# IF_TX.net
KiCad netlist of a schematic drawn in Altium Designer
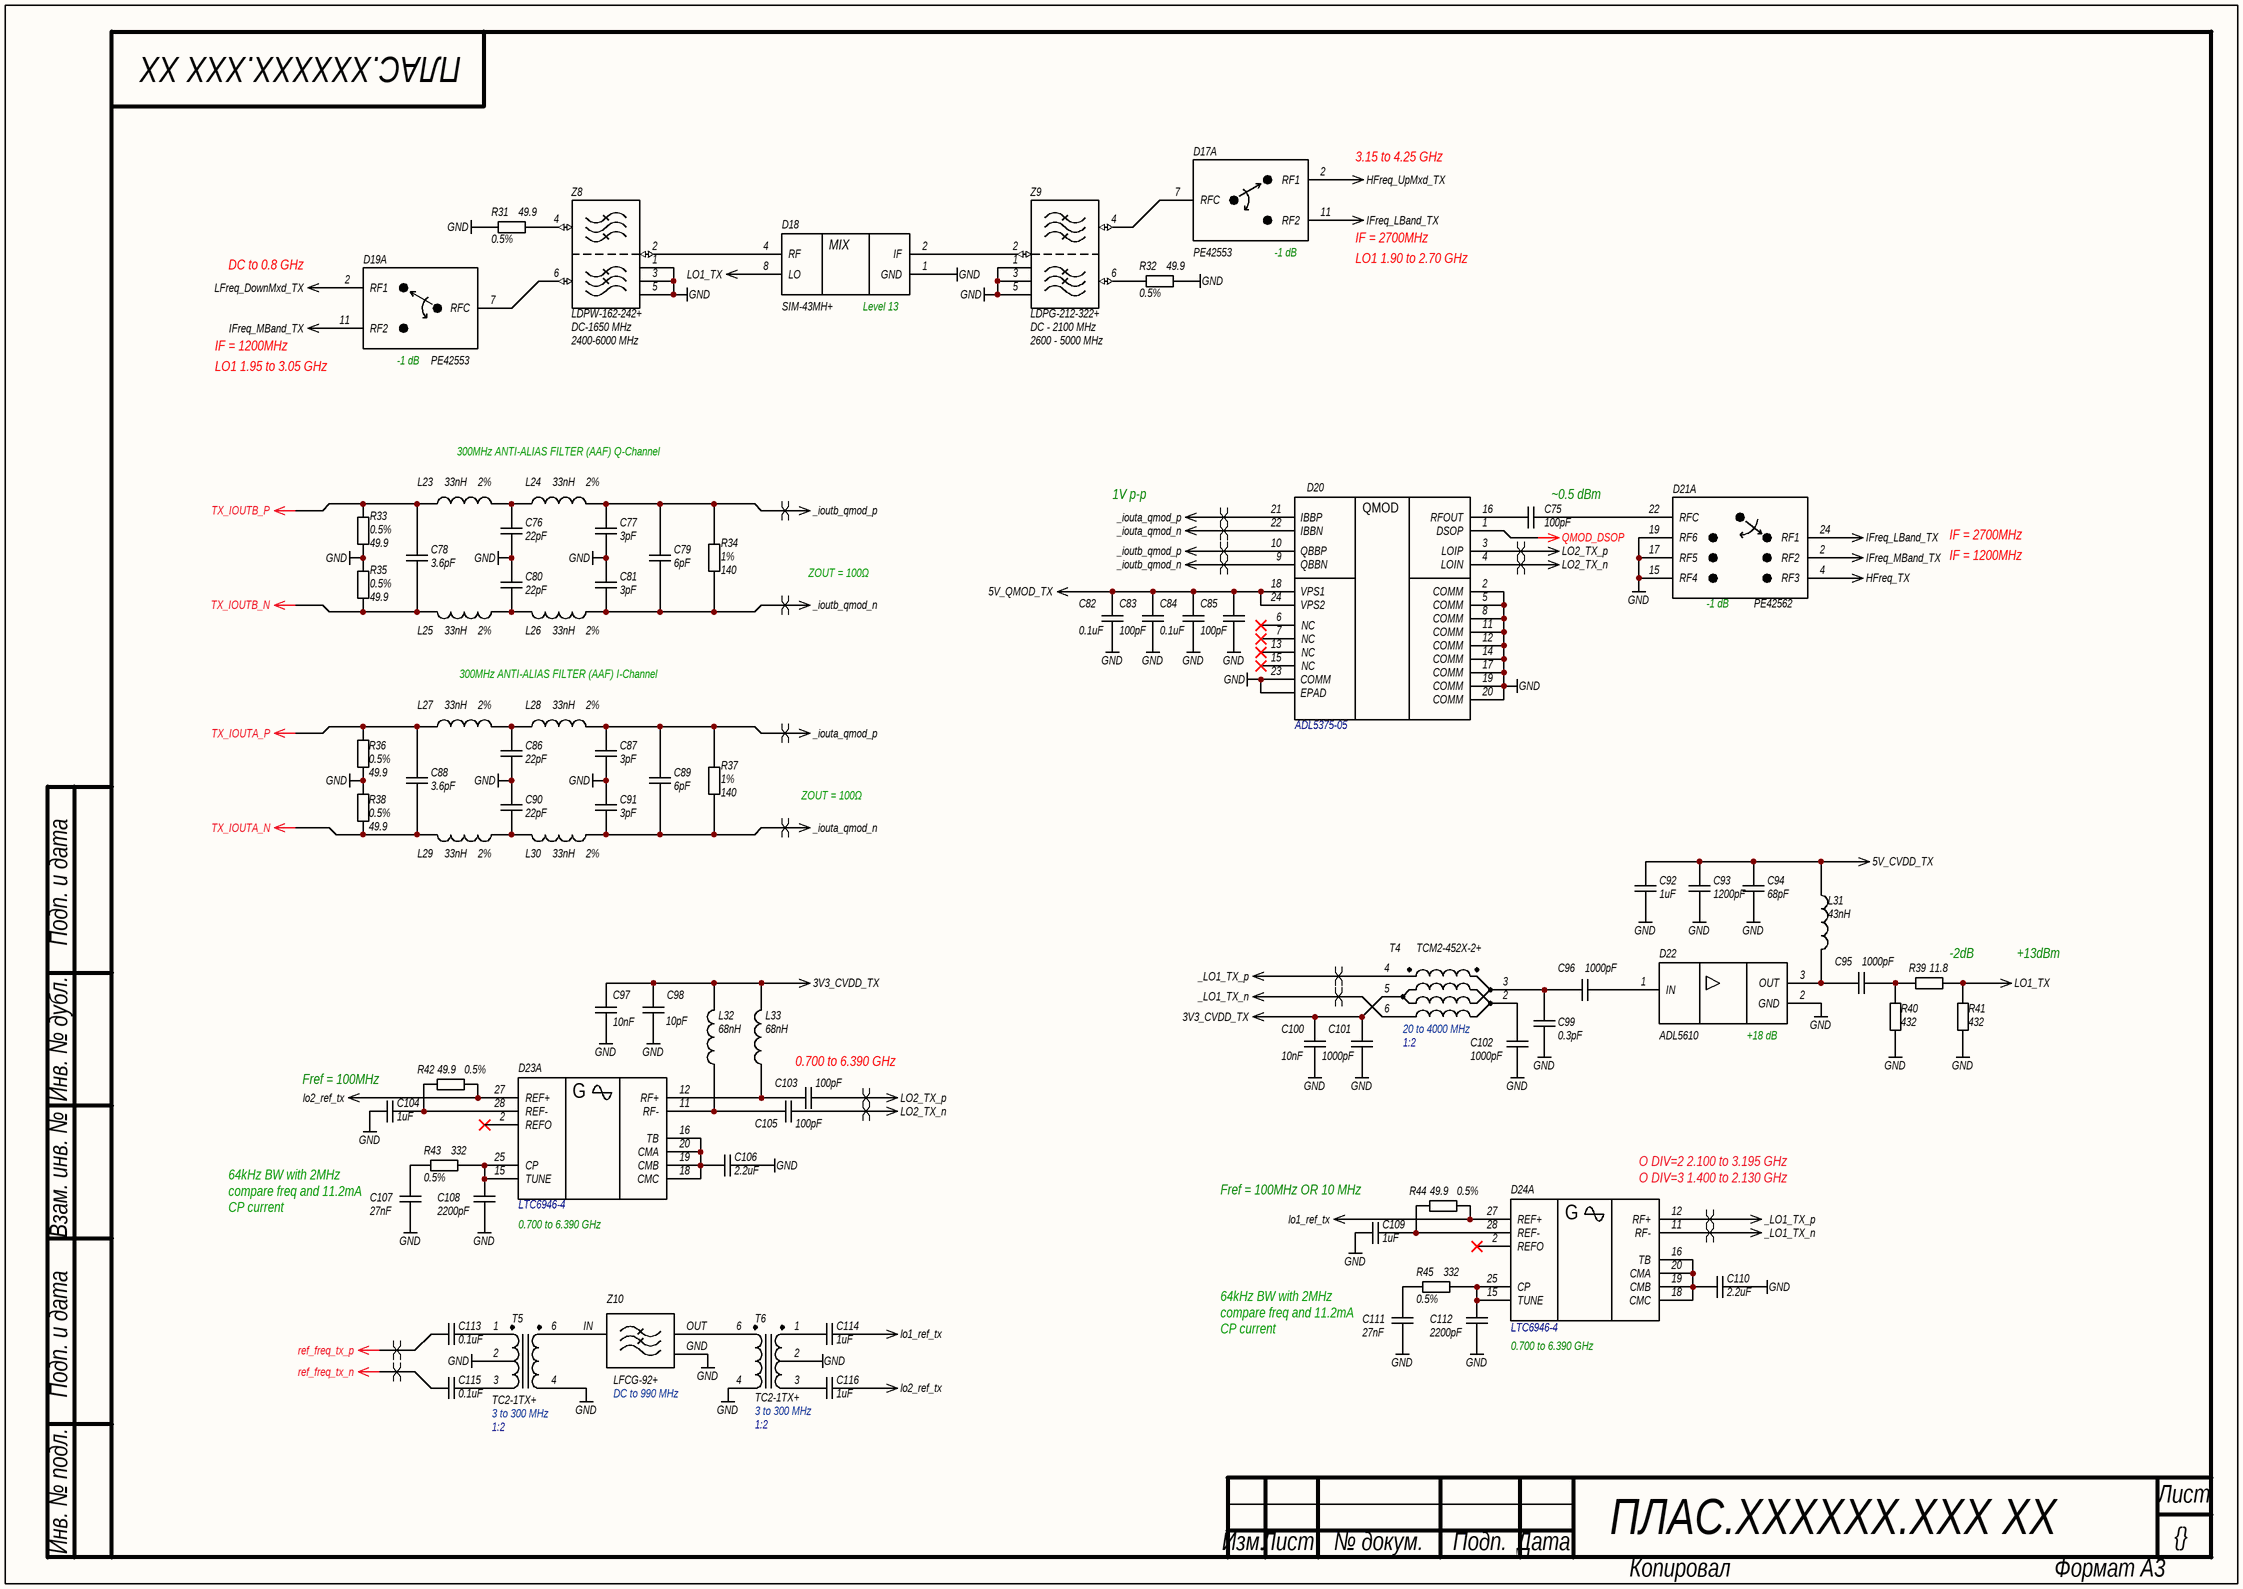
[diagram p0: IF_TX.SchDoc]

(export (version "E")
  (design (tool "Eeschema 10.0.6"))
  (components
    (comp (ref "C75")
      (value "100pF")
      (footprint "C0402")
      (description "SMD Capacitor")
      (fields (field (name "MANUFACTURER") "Murata") (field (name "TOLERANCE") "1%"))
      (libsource (lib "Kintex_SDR") (part "CAP"))
    )
    (comp (ref "C76")
      (value "22pF")
      (footprint "C0402")
      (description "SMD Capacitor")
      (fields (field (name "MANUFACTURER") "Murata") (field (name "TOLERANCE") "1%"))
      (libsource (lib "Kintex_SDR") (part "CAP"))
    )
    (comp (ref "C77")
      (value "3pF")
      (footprint "C0402")
      (description "SMD Capacitor")
      (fields (field (name "MANUFACTURER") "Murata") (field (name "TOLERANCE") "±0.25pF"))
      (libsource (lib "Kintex_SDR") (part "CAP"))
    )
    (comp (ref "C78")
      (value "3.6pF")
      (footprint "C0402")
      (description "SMD Capacitor")
      (fields (field (name "MANUFACTURER") "Murata") (field (name "TOLERANCE") "±0.25pF"))
      (libsource (lib "Kintex_SDR") (part "CAP"))
    )
    (comp (ref "C79")
      (value "6pF")
      (footprint "C0402")
      (description "SMD Capacitor")
      (fields (field (name "MANUFACTURER") "Murata") (field (name "TOLERANCE") "±0.5pF"))
      (libsource (lib "Kintex_SDR") (part "CAP"))
    )
    (comp (ref "C80")
      (value "22pF")
      (footprint "C0402")
      (description "SMD Capacitor")
      (fields (field (name "MANUFACTURER") "Murata") (field (name "TOLERANCE") "1%"))
      (libsource (lib "Kintex_SDR") (part "CAP"))
    )
    (comp (ref "C81")
      (value "3pF")
      (footprint "C0402")
      (description "SMD Capacitor")
      (fields (field (name "MANUFACTURER") "Murata") (field (name "TOLERANCE") "±0.25pF"))
      (libsource (lib "Kintex_SDR") (part "CAP"))
    )
    (comp (ref "C82")
      (value "0.1uF")
      (footprint "C0402")
      (description "SMD Capacitor")
      (fields (field (name "MANUFACTURER") "Murata") (field (name "TOLERANCE") "10%"))
      (libsource (lib "Kintex_SDR") (part "CAP"))
    )
    (comp (ref "C83")
      (value "100pF")
      (footprint "C0402")
      (description "SMD Capacitor")
      (fields (field (name "MANUFACTURER") "Murata") (field (name "TOLERANCE") "1%"))
      (libsource (lib "Kintex_SDR") (part "CAP"))
    )
    (comp (ref "C84")
      (value "0.1uF")
      (footprint "C0402")
      (description "SMD Capacitor")
      (fields (field (name "MANUFACTURER") "Murata") (field (name "TOLERANCE") "10%"))
      (libsource (lib "Kintex_SDR") (part "CAP"))
    )
    (comp (ref "C85")
      (value "100pF")
      (footprint "C0402")
      (description "SMD Capacitor")
      (fields (field (name "MANUFACTURER") "Murata") (field (name "TOLERANCE") "1%"))
      (libsource (lib "Kintex_SDR") (part "CAP"))
    )
    (comp (ref "C86")
      (value "22pF")
      (footprint "C0402")
      (description "SMD Capacitor")
      (fields (field (name "MANUFACTURER") "Murata") (field (name "TOLERANCE") "1%"))
      (libsource (lib "Kintex_SDR") (part "CAP"))
    )
    (comp (ref "C87")
      (value "3pF")
      (footprint "C0402")
      (description "SMD Capacitor")
      (fields (field (name "MANUFACTURER") "Murata") (field (name "TOLERANCE") "±0.25pF"))
      (libsource (lib "Kintex_SDR") (part "CAP"))
    )
    (comp (ref "C88")
      (value "3.6pF")
      (footprint "C0402")
      (description "SMD Capacitor")
      (fields (field (name "MANUFACTURER") "Murata") (field (name "TOLERANCE") "±0.25pF"))
      (libsource (lib "Kintex_SDR") (part "CAP"))
    )
    (comp (ref "C89")
      (value "6pF")
      (footprint "C0402")
      (description "SMD Capacitor")
      (fields (field (name "MANUFACTURER") "Murata") (field (name "TOLERANCE") "±0.5pF"))
      (libsource (lib "Kintex_SDR") (part "CAP"))
    )
    (comp (ref "C90")
      (value "22pF")
      (footprint "C0402")
      (description "SMD Capacitor")
      (fields (field (name "MANUFACTURER") "Murata") (field (name "TOLERANCE") "1%"))
      (libsource (lib "Kintex_SDR") (part "CAP"))
    )
    (comp (ref "C91")
      (value "3pF")
      (footprint "C0402")
      (description "SMD Capacitor")
      (fields (field (name "MANUFACTURER") "Murata") (field (name "TOLERANCE") "±0.25pF"))
      (libsource (lib "Kintex_SDR") (part "CAP"))
    )
    (comp (ref "C92")
      (value "1uF")
      (footprint "C0805")
      (description "SMD Capacitor")
      (fields (field (name "MANUFACTURER") "Murata") (field (name "TOLERANCE") "10%"))
      (libsource (lib "Kintex_SDR") (part "CAP"))
    )
    (comp (ref "C93")
      (value "1200pF")
      (footprint "C0603")
      (description "SMD Capacitor")
      (fields (field (name "MANUFACTURER") "Murata") (field (name "TOLERANCE") "±2%"))
      (libsource (lib "Kintex_SDR") (part "CAP"))
    )
    (comp (ref "C94")
      (value "68pF")
      (footprint "C0402")
      (description "SMD Capacitor")
      (fields (field (name "MANUFACTURER") "Murata") (field (name "TOLERANCE") "±1%"))
      (libsource (lib "Kintex_SDR") (part "CAP"))
    )
    (comp (ref "C95")
      (value "1000pF")
      (footprint "C0402")
      (description "SMD Capacitor")
      (fields (field (name "MANUFACTURER") "Murata") (field (name "TOLERANCE") "5%"))
      (libsource (lib "Kintex_SDR") (part "CAP"))
    )
    (comp (ref "C96")
      (value "1000pF")
      (footprint "C0402")
      (description "SMD Capacitor")
      (fields (field (name "MANUFACTURER") "Murata") (field (name "TOLERANCE") "5%"))
      (libsource (lib "Kintex_SDR") (part "CAP"))
    )
    (comp (ref "C97")
      (value "10nF")
      (footprint "C0402")
      (description "SMD Capacitor")
      (fields (field (name "MANUFACTURER") "Murata") (field (name "TOLERANCE") "10%"))
      (libsource (lib "Kintex_SDR") (part "CAP"))
    )
    (comp (ref "C98")
      (value "10pF")
      (footprint "C0402")
      (description "SMD Capacitor")
      (fields (field (name "MANUFACTURER") "Murata") (field (name "TOLERANCE") "1%"))
      (libsource (lib "Kintex_SDR") (part "CAP"))
    )
    (comp (ref "C99")
      (value "0.3pF")
      (footprint "C0402")
      (description "SMD Capacitor")
      (fields (field (name "MANUFACTURER") "Murata") (field (name "TOLERANCE") "±0.05pF"))
      (libsource (lib "Kintex_SDR") (part "CAP"))
    )
    (comp (ref "C100")
      (value "10nF")
      (footprint "C0402")
      (description "SMD Capacitor")
      (fields (field (name "MANUFACTURER") "Murata") (field (name "TOLERANCE") "10%"))
      (libsource (lib "Kintex_SDR") (part "CAP"))
    )
    (comp (ref "C101")
      (value "1000pF")
      (footprint "C0402")
      (description "SMD Capacitor")
      (fields (field (name "MANUFACTURER") "Murata") (field (name "TOLERANCE") "5%"))
      (libsource (lib "Kintex_SDR") (part "CAP"))
    )
    (comp (ref "C102")
      (value "1000pF")
      (footprint "C0402")
      (description "SMD Capacitor")
      (fields (field (name "MANUFACTURER") "Murata") (field (name "TOLERANCE") "5%"))
      (libsource (lib "Kintex_SDR") (part "CAP"))
    )
    (comp (ref "C103")
      (value "100pF")
      (footprint "C0402")
      (description "SMD Capacitor")
      (fields (field (name "MANUFACTURER") "Murata") (field (name "TOLERANCE") "1%"))
      (libsource (lib "Kintex_SDR") (part "CAP"))
    )
    (comp (ref "C104")
      (value "1uF")
      (footprint "C0805")
      (description "SMD Capacitor")
      (fields (field (name "MANUFACTURER") "Murata") (field (name "TOLERANCE") "10%"))
      (libsource (lib "Kintex_SDR") (part "CAP"))
    )
    (comp (ref "C105")
      (value "100pF")
      (footprint "C0402")
      (description "SMD Capacitor")
      (fields (field (name "MANUFACTURER") "Murata") (field (name "TOLERANCE") "1%"))
      (libsource (lib "Kintex_SDR") (part "CAP"))
    )
    (comp (ref "C106")
      (value "2.2uF")
      (footprint "C0603")
      (description "SMD Capacitor")
      (fields (field (name "MANUFACTURER") "Murata") (field (name "TOLERANCE") "10%"))
      (libsource (lib "Kintex_SDR") (part "CAP"))
    )
    (comp (ref "C107")
      (value "27nF")
      (footprint "C1206")
      (description "SMD Capacitor")
      (fields (field (name "MANUFACTURER") "Murata") (field (name "TOLERANCE") "±5%"))
      (libsource (lib "Kintex_SDR") (part "CAP"))
    )
    (comp (ref "C108")
      (value "2200pF")
      (footprint "C0603")
      (description "SMD Capacitor")
      (fields (field (name "MANUFACTURER") "Murata") (field (name "TOLERANCE") "1%"))
      (libsource (lib "Kintex_SDR") (part "CAP"))
    )
    (comp (ref "C109")
      (value "1uF")
      (footprint "C0805")
      (description "SMD Capacitor")
      (fields (field (name "MANUFACTURER") "Murata") (field (name "TOLERANCE") "10%"))
      (libsource (lib "Kintex_SDR") (part "CAP"))
    )
    (comp (ref "C110")
      (value "2.2uF")
      (footprint "C0603")
      (description "SMD Capacitor")
      (fields (field (name "MANUFACTURER") "Murata") (field (name "TOLERANCE") "10%"))
      (libsource (lib "Kintex_SDR") (part "CAP"))
    )
    (comp (ref "C111")
      (value "27nF")
      (footprint "C1206")
      (description "SMD Capacitor")
      (fields (field (name "MANUFACTURER") "Murata") (field (name "TOLERANCE") "±5%"))
      (libsource (lib "Kintex_SDR") (part "CAP"))
    )
    (comp (ref "C112")
      (value "2200pF")
      (footprint "C0603")
      (description "SMD Capacitor")
      (fields (field (name "MANUFACTURER") "Murata") (field (name "TOLERANCE") "1%"))
      (libsource (lib "Kintex_SDR") (part "CAP"))
    )
    (comp (ref "C113")
      (value "0.1uF")
      (footprint "C0402")
      (description "SMD Capacitor")
      (fields (field (name "MANUFACTURER") "Murata") (field (name "TOLERANCE") "10%"))
      (libsource (lib "Kintex_SDR") (part "CAP"))
    )
    (comp (ref "C114")
      (value "1uF")
      (footprint "C0805")
      (description "SMD Capacitor")
      (fields (field (name "MANUFACTURER") "Murata") (field (name "TOLERANCE") "10%"))
      (libsource (lib "Kintex_SDR") (part "CAP"))
    )
    (comp (ref "C115")
      (value "0.1uF")
      (footprint "C0402")
      (description "SMD Capacitor")
      (fields (field (name "MANUFACTURER") "Murata") (field (name "TOLERANCE") "10%"))
      (libsource (lib "Kintex_SDR") (part "CAP"))
    )
    (comp (ref "C116")
      (value "1uF")
      (footprint "C0805")
      (description "SMD Capacitor")
      (fields (field (name "MANUFACTURER") "Murata") (field (name "TOLERANCE") "10%"))
      (libsource (lib "Kintex_SDR") (part "CAP"))
    )
    (comp (ref "D17")
      (value "PE42553")
      (footprint "QFN-16")
      (description "HaRPTM technology-enhanced absorptive SPDT")
      (fields (field (name "MANUFACTURER") "Peregrine Technical Solutions"))
      (libsource (lib "") (part "PE42553_1"))
    )
    (comp (ref "D18")
      (value "SIM-43MH+")
      (footprint "DBLib:SIM-43MH+")
      (description "Frequency Mixer")
      (fields (field (name "MANUFACTURER") "Mini-Circuits"))
      (libsource (lib "DBLib") (part "SIM-43MH+"))
    )
    (comp (ref "D19")
      (value "PE42553")
      (footprint "QFN-16")
      (description "HaRPTM technology-enhanced absorptive SPDT")
      (fields (field (name "MANUFACTURER") "Peregrine Technical Solutions"))
      (libsource (lib "DBLib") (part "PE42553"))
    )
    (comp (ref "D20")
      (value "ADL5375")
      (footprint "LFCSP-24")
      (description "Broadband Quadrature Modulator")
      (fields
        (field (name "MANUFACTURER") "Analog Devices")
        (field (name "VOLTAGE") "4.75 V to 5.25 V")
        (field (name "NAME") "ADL5375-05")
      )
      (libsource (lib "DBLib") (part "ADL5375"))
    )
    (comp (ref "D21")
      (value "PE42562")
      (footprint "QFN-24")
      (description "The PE42582 is a HaRP™ technology-enhanced absorptive SP6T RF switch")
      (fields (field (name "MANUFACTURER") "Peregrine Technical Solutions"))
      (libsource (lib "DBLib") (part "PE42562"))
    )
    (comp (ref "D22")
      (value "ADL5610")
      (footprint "DBLib:ADL5610")
      (description "RF/IF Gain Block")
      (fields (field (name "MANUFACTURER") "Analog Devices"))
      (libsource (lib "DBLib") (part "ADL5610"))
    )
    (comp (ref "D23")
      (value "LTC6946")
      (footprint "QFN-28")
      (description "The LTC®6946 is a high performance, low noise, 6.39GHz  phase-locked loop (PLL)")
      (fields
        (field (name "MANUFACTURER") "Linear Technology")
        (field (name "VOLTAGE") "3.15 V ~ 5.25 V")
        (field (name "NAME") "LTC6946-4")
        (field (name "FREQUENCY RANGE") "0.700 to 6.390 GHz")
      )
      (libsource (lib "DBLib") (part "LTC6946"))
    )
    (comp (ref "D24")
      (value "LTC6946")
      (footprint "QFN-28")
      (description "The LTC®6946 is a high performance, low noise, 6.39GHz  phase-locked loop (PLL)")
      (fields
        (field (name "MANUFACTURER") "Linear Technology")
        (field (name "VOLTAGE") "3.15 V ~ 5.25 V")
        (field (name "NAME") "LTC6946-4")
        (field (name "FREQUENCY RANGE") "0.700 to 6.390 GHz")
      )
      (libsource (lib "DBLib") (part "LTC6946"))
    )
    (comp (ref "L23")
      (value "33nH")
      (footprint "DBLib:L0603_HP")
      (description "Chip SMD Inductor")
      (fields
        (field (name "MANUFACTURER") "Coilcraft")
        (field (name "TOLERANCE") "2%")
        (field (name "Comment") "Inductor RF")
      )
      (libsource (lib "DBLib") (part "Inductor RF"))
    )
    (comp (ref "L24")
      (value "33nH")
      (footprint "DBLib:L0603_HP")
      (description "Chip SMD Inductor")
      (fields
        (field (name "MANUFACTURER") "Coilcraft")
        (field (name "TOLERANCE") "2%")
        (field (name "Comment") "Inductor RF")
      )
      (libsource (lib "DBLib") (part "Inductor RF"))
    )
    (comp (ref "L25")
      (value "33nH")
      (footprint "DBLib:L0603_HP")
      (description "Chip SMD Inductor")
      (fields
        (field (name "MANUFACTURER") "Coilcraft")
        (field (name "TOLERANCE") "2%")
        (field (name "Comment") "Inductor RF")
      )
      (libsource (lib "") (part "Inductor RF_1"))
    )
    (comp (ref "L26")
      (value "33nH")
      (footprint "DBLib:L0603_HP")
      (description "Chip SMD Inductor")
      (fields
        (field (name "MANUFACTURER") "Coilcraft")
        (field (name "TOLERANCE") "2%")
        (field (name "Comment") "Inductor RF")
      )
      (libsource (lib "") (part "Inductor RF_1"))
    )
    (comp (ref "L27")
      (value "33nH")
      (footprint "DBLib:L0603_HP")
      (description "Chip SMD Inductor")
      (fields
        (field (name "MANUFACTURER") "Coilcraft")
        (field (name "TOLERANCE") "2%")
        (field (name "Comment") "Inductor RF")
      )
      (libsource (lib "DBLib") (part "Inductor RF"))
    )
    (comp (ref "L28")
      (value "33nH")
      (footprint "DBLib:L0603_HP")
      (description "Chip SMD Inductor")
      (fields
        (field (name "MANUFACTURER") "Coilcraft")
        (field (name "TOLERANCE") "2%")
        (field (name "Comment") "Inductor RF")
      )
      (libsource (lib "DBLib") (part "Inductor RF"))
    )
    (comp (ref "L29")
      (value "33nH")
      (footprint "DBLib:L0603_HP")
      (description "Chip SMD Inductor")
      (fields
        (field (name "MANUFACTURER") "Coilcraft")
        (field (name "TOLERANCE") "2%")
        (field (name "Comment") "Inductor RF")
      )
      (libsource (lib "") (part "Inductor RF_1"))
    )
    (comp (ref "L30")
      (value "33nH")
      (footprint "DBLib:L0603_HP")
      (description "Chip SMD Inductor")
      (fields
        (field (name "MANUFACTURER") "Coilcraft")
        (field (name "TOLERANCE") "2%")
        (field (name "Comment") "Inductor RF")
      )
      (libsource (lib "") (part "Inductor RF_1"))
    )
    (comp (ref "L31")
      (value "43nH")
      (footprint "DBLib:L0603_HP")
      (description "Chip SMD Inductor")
      (fields (field (name "MANUFACTURER") "Coilcraft") (field (name "TOLERANCE") "5%"))
      (libsource (lib "") (part "Inductor RF_1"))
    )
    (comp (ref "L32")
      (value "68nH")
      (footprint "DBLib:L0603_HP")
      (description "Chip SMD Inductor")
      (fields (field (name "MANUFACTURER") "Coilcraft") (field (name "TOLERANCE") "5%"))
      (libsource (lib "DBLib") (part "Inductor RF"))
    )
    (comp (ref "L33")
      (value "68nH")
      (footprint "DBLib:L0603_HP")
      (description "Chip SMD Inductor")
      (fields (field (name "MANUFACTURER") "Coilcraft") (field (name "TOLERANCE") "5%"))
      (libsource (lib "DBLib") (part "Inductor RF"))
    )
    (comp (ref "R31")
      (value "49.9")
      (footprint "R0402")
      (description "SMD Resistor")
      (fields
        (field (name "POWER") "0.063 Wt")
        (field (name "TOLERANCE") "0.5%")
        (field (name "MANUFACTURER") "Panasonic Electronic Components")
      )
      (libsource (lib "") (part "RES_2"))
    )
    (comp (ref "R32")
      (value "49.9")
      (footprint "R0402")
      (description "SMD Resistor")
      (fields
        (field (name "POWER") "0.063 Wt")
        (field (name "TOLERANCE") "0.5%")
        (field (name "MANUFACTURER") "Panasonic Electronic Components")
      )
      (libsource (lib "Kintex_SDR") (part "RES"))
    )
    (comp (ref "R33")
      (value "49.9")
      (footprint "R0402")
      (description "SMD Resistor")
      (fields
        (field (name "POWER") "0.063 Wt")
        (field (name "TOLERANCE") "0.5%")
        (field (name "MANUFACTURER") "Panasonic Electronic Components")
      )
      (libsource (lib "Kintex_SDR") (part "RES"))
    )
    (comp (ref "R34")
      (value "140")
      (footprint "R0402")
      (description "SMD Resistor")
      (fields
        (field (name "POWER") "0.1 Wt")
        (field (name "TOLERANCE") "1%")
        (field (name "MANUFACTURER") "Panasonic Electronic Components")
      )
      (libsource (lib "Kintex_SDR") (part "RES"))
    )
    (comp (ref "R35")
      (value "49.9")
      (footprint "R0402")
      (description "SMD Resistor")
      (fields
        (field (name "POWER") "0.063 Wt")
        (field (name "TOLERANCE") "0.5%")
        (field (name "MANUFACTURER") "Panasonic Electronic Components")
      )
      (libsource (lib "Kintex_SDR") (part "RES"))
    )
    (comp (ref "R36")
      (value "49.9")
      (footprint "R0402")
      (description "SMD Resistor")
      (fields
        (field (name "POWER") "0.063 Wt")
        (field (name "TOLERANCE") "0.5%")
        (field (name "MANUFACTURER") "Panasonic Electronic Components")
      )
      (libsource (lib "Kintex_SDR") (part "RES"))
    )
    (comp (ref "R37")
      (value "140")
      (footprint "R0402")
      (description "SMD Resistor")
      (fields
        (field (name "POWER") "0.1 Wt")
        (field (name "TOLERANCE") "1%")
        (field (name "MANUFACTURER") "Panasonic Electronic Components")
      )
      (libsource (lib "Kintex_SDR") (part "RES"))
    )
    (comp (ref "R38")
      (value "49.9")
      (footprint "R0402")
      (description "SMD Resistor")
      (fields
        (field (name "POWER") "0.063 Wt")
        (field (name "TOLERANCE") "0.5%")
        (field (name "MANUFACTURER") "Panasonic Electronic Components")
      )
      (libsource (lib "Kintex_SDR") (part "RES"))
    )
    (comp (ref "R39")
      (value "11.8")
      (footprint "R0402")
      (description "SMD Resistor")
      (fields (field (name "POWER") "0.063 Wt") (field (name "TOLERANCE") "±1%"))
      (libsource (lib "Kintex_SDR") (part "RES"))
    )
    (comp (ref "R40")
      (value "432")
      (footprint "R0402")
      (description "SMD Resistor")
      (fields (field (name "POWER") "0.1 Wt") (field (name "TOLERANCE") "±1%"))
      (libsource (lib "") (part "RES_1"))
    )
    (comp (ref "R41")
      (value "432")
      (footprint "R0402")
      (description "SMD Resistor")
      (fields (field (name "POWER") "0.1 Wt") (field (name "TOLERANCE") "±1%"))
      (libsource (lib "") (part "RES_1"))
    )
    (comp (ref "R42")
      (value "49.9")
      (footprint "R0402")
      (description "SMD Resistor")
      (fields
        (field (name "POWER") "0.063 Wt")
        (field (name "TOLERANCE") "0.5%")
        (field (name "MANUFACTURER") "Panasonic Electronic Components")
      )
      (libsource (lib "Kintex_SDR") (part "RES"))
    )
    (comp (ref "R43")
      (value "332")
      (footprint "R0603")
      (description "SMD Resistor")
      (fields
        (field (name "POWER") "0.2 Wt")
        (field (name "TOLERANCE") "0.5%")
        (field (name "MANUFACTURER") "Panasonic Electronic Components")
      )
      (libsource (lib "Kintex_SDR") (part "RES"))
    )
    (comp (ref "R44")
      (value "49.9")
      (footprint "R0402")
      (description "SMD Resistor")
      (fields
        (field (name "POWER") "0.063 Wt")
        (field (name "TOLERANCE") "0.5%")
        (field (name "MANUFACTURER") "Panasonic Electronic Components")
      )
      (libsource (lib "Kintex_SDR") (part "RES"))
    )
    (comp (ref "R45")
      (value "332")
      (footprint "R0603")
      (description "SMD Resistor")
      (fields
        (field (name "POWER") "0.2 Wt")
        (field (name "TOLERANCE") "0.5%")
        (field (name "MANUFACTURER") "Panasonic Electronic Components")
      )
      (libsource (lib "Kintex_SDR") (part "RES"))
    )
    (comp (ref "T4")
      (value "TCM2-452X-2+")
      (footprint "DB1627")
      (description "RF Transformer")
      (fields
        (field (name "MANUFACTURER") "Mini-Circuits")
        (field (name "FREQUENCY") "20 to 4000 MHz")
        (field (name "RATIO") "1:2")
      )
      (libsource (lib "DBLib") (part "TCM2-452X-2+"))
    )
    (comp (ref "T5")
      (value "TC2-1TX+")
      (footprint "DBLib:AT1521")
      (description "RF Transformer")
      (fields
        (field (name "MANUFACTURER") "Mini-Circuits")
        (field (name "FREQUENCY") "3 to 300 MHz")
        (field (name "RATIO") "1:2")
      )
      (libsource (lib "") (part "TC2-1TX+_1"))
    )
    (comp (ref "T6")
      (value "TC2-1TX+")
      (footprint "DBLib:AT1521")
      (description "RF Transformer")
      (fields
        (field (name "MANUFACTURER") "Mini-Circuits")
        (field (name "FREQUENCY") "3 to 300 MHz")
        (field (name "RATIO") "1:2")
      )
      (libsource (lib "DBLib") (part "TC2-1TX+"))
    )
    (comp (ref "Z8")
      (value "LDPW-162-242+")
      (footprint "DBLib:JC0603C")
      (description "Diplexer")
      (fields
        (field (name "MANUFACTURER") "Mini-Circuits")
        (field (name "LOW PASS") "DC-1650 MHz")
        (field (name "HIGH PASS") "2400-6000 MHz")
      )
      (libsource (lib "DBLib") (part "LDPW-162-242+"))
    )
    (comp (ref "Z9")
      (value "LDPG-212-322+")
      (footprint "GE0805C-10")
      (description "Diplexer")
      (fields
        (field (name "MANUFACTURER") "Mini-Circuits")
        (field (name "LOW PASS") "DC - 2100 MHz")
        (field (name "HIGH PASS") "2600 - 5000 MHz")
      )
      (libsource (lib "DBLib") (part "LDPG-212-322+"))
    )
    (comp (ref "Z10")
      (value "LFCG-92+")
      (footprint "GE0805C-2")
      (description "Low Pass Filter")
      (fields (field (name "MANUFACTURER") "Mini-Circuits") (field (name "FREQUENCY") "DC to 990 MHz"))
      (libsource (lib "DBLib") (part "LFCG-92+"))
    )
  )
  (nets
    (net (code "1") (name "3V3_CVDD_TX") (class "Default")
      (node (ref "C100") (pin "2") (pinfunction "2_2") (pintype "passive"))
      (node (ref "C101") (pin "1") (pinfunction "1_1") (pintype "passive"))
      (node (ref "C97") (pin "2") (pinfunction "2_2") (pintype "passive"))
      (node (ref "C98") (pin "2") (pinfunction "2_2") (pintype "passive"))
      (node (ref "L32") (pin "2") (pinfunction "2_2") (pintype "passive"))
      (node (ref "L33") (pin "2") (pinfunction "2_2") (pintype "passive"))
      (node (ref "T4") (pin "5") (pinfunction "5_5") (pintype "passive"))
    )
    (net (code "2") (name "5V_CVDD_TX") (class "Default")
      (node (ref "C92") (pin "1") (pinfunction "1_1") (pintype "passive"))
      (node (ref "C93") (pin "2") (pinfunction "2_2") (pintype "passive"))
      (node (ref "C94") (pin "2") (pinfunction "2_2") (pintype "passive"))
      (node (ref "L31") (pin "2") (pinfunction "2_2") (pintype "passive"))
    )
    (net (code "3") (name "5V_QMOD_TX") (class "Default")
      (node (ref "C82") (pin "2") (pinfunction "2_2") (pintype "passive"))
      (node (ref "C83") (pin "2") (pinfunction "2_2") (pintype "passive"))
      (node (ref "C84") (pin "2") (pinfunction "2_2") (pintype "passive"))
      (node (ref "C85") (pin "2") (pinfunction "2_2") (pintype "passive"))
      (node (ref "D20") (pin "18") (pinfunction "VPS1_18") (pintype "passive"))
      (node (ref "D20") (pin "24") (pinfunction "VPS2_24") (pintype "passive"))
    )
    (net (code "4") (name "GND") (class "Default")
      (node (ref "C100") (pin "1") (pinfunction "1_1") (pintype "passive"))
      (node (ref "C101") (pin "2") (pinfunction "2_2") (pintype "passive"))
      (node (ref "C102") (pin "2") (pinfunction "2_2") (pintype "passive"))
      (node (ref "C104") (pin "2") (pinfunction "2_2") (pintype "passive"))
      (node (ref "C106") (pin "1") (pinfunction "1_1") (pintype "passive"))
      (node (ref "C107") (pin "1") (pinfunction "1_1") (pintype "passive"))
      (node (ref "C108") (pin "1") (pinfunction "1_1") (pintype "passive"))
      (node (ref "C109") (pin "2") (pinfunction "2_2") (pintype "passive"))
      (node (ref "C110") (pin "1") (pinfunction "1_1") (pintype "passive"))
      (node (ref "C111") (pin "1") (pinfunction "1_1") (pintype "passive"))
      (node (ref "C112") (pin "1") (pinfunction "1_1") (pintype "passive"))
      (node (ref "C76") (pin "2") (pinfunction "2_2") (pintype "passive"))
      (node (ref "C77") (pin "2") (pinfunction "2_2") (pintype "passive"))
      (node (ref "C80") (pin "1") (pinfunction "1_1") (pintype "passive"))
      (node (ref "C81") (pin "1") (pinfunction "1_1") (pintype "passive"))
      (node (ref "C82") (pin "1") (pinfunction "1_1") (pintype "passive"))
      (node (ref "C83") (pin "1") (pinfunction "1_1") (pintype "passive"))
      (node (ref "C84") (pin "1") (pinfunction "1_1") (pintype "passive"))
      (node (ref "C85") (pin "1") (pinfunction "1_1") (pintype "passive"))
      (node (ref "C86") (pin "2") (pinfunction "2_2") (pintype "passive"))
      (node (ref "C87") (pin "2") (pinfunction "2_2") (pintype "passive"))
      (node (ref "C90") (pin "1") (pinfunction "1_1") (pintype "passive"))
      (node (ref "C91") (pin "1") (pinfunction "1_1") (pintype "passive"))
      (node (ref "C92") (pin "2") (pinfunction "2_2") (pintype "passive"))
      (node (ref "C93") (pin "1") (pinfunction "1_1") (pintype "passive"))
      (node (ref "C94") (pin "1") (pinfunction "1_1") (pintype "passive"))
      (node (ref "C97") (pin "1") (pinfunction "1_1") (pintype "passive"))
      (node (ref "C98") (pin "1") (pinfunction "1_1") (pintype "passive"))
      (node (ref "C99") (pin "1") (pinfunction "1_1") (pintype "passive"))
      (node (ref "D18") (pin "1") (pinfunction "GND_1") (pintype "passive"))
      (node (ref "D20") (pin "11") (pinfunction "COMM_11") (pintype "passive"))
      (node (ref "D20") (pin "12") (pinfunction "COMM_12") (pintype "passive"))
      (node (ref "D20") (pin "14") (pinfunction "COMM_14") (pintype "passive"))
      (node (ref "D20") (pin "17") (pinfunction "COMM_17") (pintype "passive"))
      (node (ref "D20") (pin "19") (pinfunction "COMM_19") (pintype "passive"))
      (node (ref "D20") (pin "2") (pinfunction "COMM_2") (pintype "passive"))
      (node (ref "D20") (pin "20") (pinfunction "COMM_20") (pintype "passive"))
      (node (ref "D20") (pin "23") (pinfunction "COMM_23") (pintype "passive"))
      (node (ref "D20") (pin "25") (pinfunction "EPAD_25") (pintype "passive"))
      (node (ref "D20") (pin "5") (pinfunction "COMM_5") (pintype "passive"))
      (node (ref "D20") (pin "8") (pinfunction "COMM_8") (pintype "passive"))
      (node (ref "D21") (pin "15") (pinfunction "RF4_15") (pintype "passive"))
      (node (ref "D21") (pin "17") (pinfunction "RF5_17") (pintype "passive"))
      (node (ref "D21") (pin "19") (pinfunction "RF6_19") (pintype "passive"))
      (node (ref "D22") (pin "2") (pinfunction "GND_2") (pintype "passive"))
      (node (ref "R31") (pin "1") (pinfunction "1_1") (pintype "passive"))
      (node (ref "R32") (pin "1") (pinfunction "1_1") (pintype "passive"))
      (node (ref "R33") (pin "2") (pinfunction "2_2") (pintype "passive"))
      (node (ref "R35") (pin "1") (pinfunction "1_1") (pintype "passive"))
      (node (ref "R36") (pin "2") (pinfunction "2_2") (pintype "passive"))
      (node (ref "R38") (pin "1") (pinfunction "1_1") (pintype "passive"))
      (node (ref "R40") (pin "2") (pinfunction "2_2") (pintype "passive"))
      (node (ref "R41") (pin "2") (pinfunction "2_2") (pintype "passive"))
      (node (ref "T5") (pin "2") (pinfunction "2_2") (pintype "passive"))
      (node (ref "T5") (pin "4") (pinfunction "4_4") (pintype "passive"))
      (node (ref "T6") (pin "2") (pinfunction "2_2") (pintype "passive"))
      (node (ref "T6") (pin "4") (pinfunction "4_4") (pintype "passive"))
      (node (ref "Z10") (pin "GND") (pinfunction "GND_GND") (pintype "passive"))
      (node (ref "Z8") (pin "1") (pinfunction "GND_1") (pintype "passive"))
      (node (ref "Z8") (pin "3") (pinfunction "GND_3") (pintype "passive"))
      (node (ref "Z8") (pin "5") (pinfunction "GND_5") (pintype "passive"))
      (node (ref "Z9") (pin "1") (pinfunction "GND_1") (pintype "passive"))
      (node (ref "Z9") (pin "3") (pinfunction "GND_3") (pintype "passive"))
      (node (ref "Z9") (pin "5") (pinfunction "GND_5") (pintype "passive"))
    )
    (net (code "5") (name "HFreq_TX") (class "Default")
      (node (ref "D21") (pin "4") (pinfunction "RF3_4") (pintype "passive"))
    )
    (net (code "6") (name "HFreq_UpMxd_TX") (class "Default")
      (node (ref "D17") (pin "2") (pinfunction "RF1_2") (pintype "passive"))
    )
    (net (code "7") (name "IFreq_LBand_TX") (class "Default")
      (node (ref "D17") (pin "11") (pinfunction "RF2_11") (pintype "passive"))
      (node (ref "D21") (pin "24") (pinfunction "RF1_24") (pintype "passive"))
    )
    (net (code "8") (name "IFreq_MBand_TX") (class "Default")
      (node (ref "D19") (pin "11") (pinfunction "RF2_11") (pintype "passive"))
      (node (ref "D21") (pin "2") (pinfunction "RF2_2") (pintype "passive"))
    )
    (net (code "9") (name "LFreq_DownMxd_TX") (class "Default")
      (node (ref "D19") (pin "2") (pinfunction "RF1_2") (pintype "passive"))
    )
    (net (code "10") (name "LO1_TX") (class "Default")
      (node (ref "D18") (pin "8") (pinfunction "LO_8") (pintype "passive"))
      (node (ref "R39") (pin "1") (pinfunction "1_1") (pintype "passive"))
      (node (ref "R41") (pin "1") (pinfunction "1_1") (pintype "passive"))
    )
    (net (code "11") (name "LO2_TX_n") (class "Default")
      (node (ref "C105") (pin "2") (pinfunction "2_2") (pintype "passive"))
      (node (ref "D20") (pin "4") (pinfunction "LOIN_4") (pintype "passive"))
    )
    (net (code "12") (name "LO2_TX_p") (class "Default")
      (node (ref "C103") (pin "2") (pinfunction "2_2") (pintype "passive"))
      (node (ref "D20") (pin "3") (pinfunction "LOIP_3") (pintype "passive"))
    )
    (net (code "13") (name "Net-(C76-Pad1)") (class "Default")
      (node (ref "C76") (pin "1") (pinfunction "1_1") (pintype "passive"))
      (node (ref "L23") (pin "2") (pinfunction "2_2") (pintype "passive"))
      (node (ref "L24") (pin "1") (pinfunction "1_1") (pintype "passive"))
    )
    (net (code "14") (name "Net-(C80-Pad2)") (class "Default")
      (node (ref "C80") (pin "2") (pinfunction "2_2") (pintype "passive"))
      (node (ref "L25") (pin "2") (pinfunction "2_2") (pintype "passive"))
      (node (ref "L26") (pin "1") (pinfunction "1_1") (pintype "passive"))
    )
    (net (code "15") (name "Net-(C86-Pad1)") (class "Default")
      (node (ref "C86") (pin "1") (pinfunction "1_1") (pintype "passive"))
      (node (ref "L27") (pin "2") (pinfunction "2_2") (pintype "passive"))
      (node (ref "L28") (pin "1") (pinfunction "1_1") (pintype "passive"))
    )
    (net (code "16") (name "Net-(C90-Pad2)") (class "Default")
      (node (ref "C90") (pin "2") (pinfunction "2_2") (pintype "passive"))
      (node (ref "L29") (pin "2") (pinfunction "2_2") (pintype "passive"))
      (node (ref "L30") (pin "1") (pinfunction "1_1") (pintype "passive"))
    )
    (net (code "17") (name "Net-(C95-Pad2)") (class "Default")
      (node (ref "C95") (pin "2") (pinfunction "2_2") (pintype "passive"))
      (node (ref "R39") (pin "2") (pinfunction "2_2") (pintype "passive"))
      (node (ref "R40") (pin "1") (pinfunction "1_1") (pintype "passive"))
    )
    (net (code "18") (name "Net-(C96-Pad1)") (class "Default")
      (node (ref "C96") (pin "1") (pinfunction "1_1") (pintype "passive"))
      (node (ref "C99") (pin "2") (pinfunction "2_2") (pintype "passive"))
      (node (ref "T4") (pin "3") (pinfunction "3_3") (pintype "passive"))
    )
    (net (code "19") (name "Net-(C102-Pad1)") (class "Default")
      (node (ref "C102") (pin "1") (pinfunction "1_1") (pintype "passive"))
      (node (ref "T4") (pin "2") (pinfunction "2_2") (pintype "passive"))
    )
    (net (code "20") (name "Net-(C107-Pad2)") (class "Default")
      (node (ref "C107") (pin "2") (pinfunction "2_2") (pintype "passive"))
      (node (ref "R43") (pin "2") (pinfunction "2_2") (pintype "passive"))
    )
    (net (code "21") (name "Net-(C111-Pad2)") (class "Default")
      (node (ref "C111") (pin "2") (pinfunction "2_2") (pintype "passive"))
      (node (ref "R45") (pin "2") (pinfunction "2_2") (pintype "passive"))
    )
    (net (code "22") (name "Net-(C113-Pad1)") (class "Default")
      (node (ref "C113") (pin "1") (pinfunction "1_1") (pintype "passive"))
      (node (ref "T5") (pin "1") (pinfunction "1_1") (pintype "passive"))
    )
    (net (code "23") (name "Net-(C114-Pad2)") (class "Default")
      (node (ref "C114") (pin "2") (pinfunction "2_2") (pintype "passive"))
      (node (ref "T6") (pin "1") (pinfunction "1_1") (pintype "passive"))
    )
    (net (code "24") (name "Net-(C115-Pad1)") (class "Default")
      (node (ref "C115") (pin "1") (pinfunction "1_1") (pintype "passive"))
      (node (ref "T5") (pin "3") (pinfunction "3_3") (pintype "passive"))
    )
    (net (code "25") (name "Net-(C116-Pad2)") (class "Default")
      (node (ref "C116") (pin "2") (pinfunction "2_2") (pintype "passive"))
      (node (ref "T6") (pin "3") (pinfunction "3_3") (pintype "passive"))
    )
    (net (code "26") (name "Net-(D17A-RFC)") (class "Default")
      (node (ref "D17") (pin "7") (pinfunction "RFC_7") (pintype "passive"))
      (node (ref "Z9") (pin "4") (pinfunction "4_4") (pintype "bidirectional"))
    )
    (net (code "27") (name "Net-(D18-IF)") (class "Default")
      (node (ref "D18") (pin "2") (pinfunction "IF_2") (pintype "passive"))
      (node (ref "Z9") (pin "2") (pinfunction "2_2") (pintype "bidirectional"))
    )
    (net (code "28") (name "Net-(D18-RF)") (class "Default")
      (node (ref "D18") (pin "4") (pinfunction "RF_4") (pintype "passive"))
      (node (ref "Z8") (pin "2") (pinfunction "2_2") (pintype "bidirectional"))
    )
    (net (code "29") (name "Net-(D19A-RFC)") (class "Default")
      (node (ref "D19") (pin "7") (pinfunction "RFC_7") (pintype "passive"))
      (node (ref "Z8") (pin "6") (pinfunction "6_6") (pintype "bidirectional"))
    )
    (net (code "30") (name "Net-(D20-RFOUT)") (class "Default")
      (node (ref "C75") (pin "1") (pinfunction "1_1") (pintype "passive"))
      (node (ref "D20") (pin "16") (pinfunction "RFOUT_16") (pintype "passive"))
    )
    (net (code "31") (name "Net-(D21A-RFC)") (class "Default")
      (node (ref "C75") (pin "2") (pinfunction "2_2") (pintype "passive"))
      (node (ref "D21") (pin "22") (pinfunction "RFC_22") (pintype "passive"))
    )
    (net (code "32") (name "Net-(D22-IN)") (class "Default")
      (node (ref "C96") (pin "2") (pinfunction "2_2") (pintype "passive"))
      (node (ref "D22") (pin "1") (pinfunction "IN_1") (pintype "passive"))
    )
    (net (code "33") (name "Net-(D22-OUT)") (class "Default")
      (node (ref "C95") (pin "1") (pinfunction "1_1") (pintype "passive"))
      (node (ref "D22") (pin "3") (pinfunction "OUT_3") (pintype "passive"))
      (node (ref "L31") (pin "1") (pinfunction "1_1") (pintype "passive"))
    )
    (net (code "34") (name "Net-(D23A-CMA)") (class "Default")
      (node (ref "C106") (pin "2") (pinfunction "2_2") (pintype "passive"))
      (node (ref "D23") (pin "16") (pinfunction "TB_16") (pintype "passive"))
      (node (ref "D23") (pin "18") (pinfunction "CMC_18") (pintype "passive"))
      (node (ref "D23") (pin "19") (pinfunction "CMB_19") (pintype "passive"))
      (node (ref "D23") (pin "20") (pinfunction "CMA_20") (pintype "passive"))
    )
    (net (code "35") (name "Net-(D23A-CP)") (class "Default")
      (node (ref "C108") (pin "2") (pinfunction "2_2") (pintype "passive"))
      (node (ref "D23") (pin "15") (pinfunction "TUNE_15") (pintype "passive"))
      (node (ref "D23") (pin "25") (pinfunction "CP_25") (pintype "passive"))
      (node (ref "R43") (pin "1") (pinfunction "1_1") (pintype "passive"))
    )
    (net (code "36") (name "Net-(D23A-REF-)") (class "Default")
      (node (ref "C104") (pin "1") (pinfunction "1_1") (pintype "passive"))
      (node (ref "D23") (pin "28") (pinfunction "REF-_28") (pintype "passive"))
      (node (ref "R42") (pin "2") (pinfunction "2_2") (pintype "passive"))
    )
    (net (code "37") (name "Net-(D23A-RF+)") (class "Default")
      (node (ref "C103") (pin "1") (pinfunction "1_1") (pintype "passive"))
      (node (ref "D23") (pin "12") (pinfunction "RF+_12") (pintype "passive"))
      (node (ref "L33") (pin "1") (pinfunction "1_1") (pintype "passive"))
    )
    (net (code "38") (name "Net-(D23A-RF-)") (class "Default")
      (node (ref "C105") (pin "1") (pinfunction "1_1") (pintype "passive"))
      (node (ref "D23") (pin "11") (pinfunction "RF-_11") (pintype "passive"))
      (node (ref "L32") (pin "1") (pinfunction "1_1") (pintype "passive"))
    )
    (net (code "39") (name "Net-(D24A-CMA)") (class "Default")
      (node (ref "C110") (pin "2") (pinfunction "2_2") (pintype "passive"))
      (node (ref "D24") (pin "16") (pinfunction "TB_16") (pintype "passive"))
      (node (ref "D24") (pin "18") (pinfunction "CMC_18") (pintype "passive"))
      (node (ref "D24") (pin "19") (pinfunction "CMB_19") (pintype "passive"))
      (node (ref "D24") (pin "20") (pinfunction "CMA_20") (pintype "passive"))
    )
    (net (code "40") (name "Net-(D24A-CP)") (class "Default")
      (node (ref "C112") (pin "2") (pinfunction "2_2") (pintype "passive"))
      (node (ref "D24") (pin "15") (pinfunction "TUNE_15") (pintype "passive"))
      (node (ref "D24") (pin "25") (pinfunction "CP_25") (pintype "passive"))
      (node (ref "R45") (pin "1") (pinfunction "1_1") (pintype "passive"))
    )
    (net (code "41") (name "Net-(D24A-REF-)") (class "Default")
      (node (ref "C109") (pin "1") (pinfunction "1_1") (pintype "passive"))
      (node (ref "D24") (pin "28") (pinfunction "REF-_28") (pintype "passive"))
      (node (ref "R44") (pin "2") (pinfunction "2_2") (pintype "passive"))
    )
    (net (code "42") (name "Net-(R31-Pad2)") (class "Default")
      (node (ref "R31") (pin "2") (pinfunction "2_2") (pintype "passive"))
      (node (ref "Z8") (pin "4") (pinfunction "4_4") (pintype "bidirectional"))
    )
    (net (code "43") (name "Net-(R32-Pad2)") (class "Default")
      (node (ref "R32") (pin "2") (pinfunction "2_2") (pintype "passive"))
      (node (ref "Z9") (pin "6") (pinfunction "6_6") (pintype "bidirectional"))
    )
    (net (code "44") (name "Net-(T5-Pad6)") (class "Default")
      (node (ref "T5") (pin "6") (pinfunction "6_6") (pintype "passive"))
      (node (ref "Z10") (pin "IN") (pinfunction "IN_IN") (pintype "passive"))
    )
    (net (code "45") (name "Net-(T6-Pad6)") (class "Default")
      (node (ref "T6") (pin "6") (pinfunction "6_6") (pintype "passive"))
      (node (ref "Z10") (pin "OUT") (pinfunction "OUT_OUT") (pintype "passive"))
    )
    (net (code "46") (name "QMOD_DSOP") (class "Default")
      (node (ref "D20") (pin "1") (pinfunction "DSOP_1") (pintype "passive"))
    )
    (net (code "47") (name "TX_IOUTA_N") (class "Default")
      (node (ref "C88") (pin "2") (pinfunction "2_2") (pintype "passive"))
      (node (ref "L29") (pin "1") (pinfunction "1_1") (pintype "passive"))
      (node (ref "R38") (pin "2") (pinfunction "2_2") (pintype "passive"))
    )
    (net (code "48") (name "TX_IOUTA_P") (class "Default")
      (node (ref "C88") (pin "1") (pinfunction "1_1") (pintype "passive"))
      (node (ref "L27") (pin "1") (pinfunction "1_1") (pintype "passive"))
      (node (ref "R36") (pin "1") (pinfunction "1_1") (pintype "passive"))
    )
    (net (code "49") (name "TX_IOUTB_N") (class "Default")
      (node (ref "C78") (pin "2") (pinfunction "2_2") (pintype "passive"))
      (node (ref "L25") (pin "1") (pinfunction "1_1") (pintype "passive"))
      (node (ref "R35") (pin "2") (pinfunction "2_2") (pintype "passive"))
    )
    (net (code "50") (name "TX_IOUTB_P") (class "Default")
      (node (ref "C78") (pin "1") (pinfunction "1_1") (pintype "passive"))
      (node (ref "L23") (pin "1") (pinfunction "1_1") (pintype "passive"))
      (node (ref "R33") (pin "1") (pinfunction "1_1") (pintype "passive"))
    )
    (net (code "51") (name "_LO1_TX_n") (class "Default")
      (node (ref "D24") (pin "11") (pinfunction "RF-_11") (pintype "passive"))
      (node (ref "T4") (pin "6") (pinfunction "6_6") (pintype "passive"))
    )
    (net (code "52") (name "_LO1_TX_p") (class "Default")
      (node (ref "D24") (pin "12") (pinfunction "RF+_12") (pintype "passive"))
      (node (ref "T4") (pin "4") (pinfunction "4_4") (pintype "passive"))
    )
    (net (code "53") (name "_iouta_qmod_n") (class "Default")
      (node (ref "C89") (pin "2") (pinfunction "2_2") (pintype "passive"))
      (node (ref "C91") (pin "2") (pinfunction "2_2") (pintype "passive"))
      (node (ref "D20") (pin "22") (pinfunction "IBBN_22") (pintype "passive"))
      (node (ref "L30") (pin "2") (pinfunction "2_2") (pintype "passive"))
      (node (ref "R37") (pin "2") (pinfunction "2_2") (pintype "passive"))
    )
    (net (code "54") (name "_iouta_qmod_p") (class "Default")
      (node (ref "C87") (pin "1") (pinfunction "1_1") (pintype "passive"))
      (node (ref "C89") (pin "1") (pinfunction "1_1") (pintype "passive"))
      (node (ref "D20") (pin "21") (pinfunction "IBBP_21") (pintype "passive"))
      (node (ref "L28") (pin "2") (pinfunction "2_2") (pintype "passive"))
      (node (ref "R37") (pin "1") (pinfunction "1_1") (pintype "passive"))
    )
    (net (code "55") (name "_ioutb_qmod_n") (class "Default")
      (node (ref "C79") (pin "2") (pinfunction "2_2") (pintype "passive"))
      (node (ref "C81") (pin "2") (pinfunction "2_2") (pintype "passive"))
      (node (ref "D20") (pin "9") (pinfunction "QBBN_9") (pintype "passive"))
      (node (ref "L26") (pin "2") (pinfunction "2_2") (pintype "passive"))
      (node (ref "R34") (pin "2") (pinfunction "2_2") (pintype "passive"))
    )
    (net (code "56") (name "_ioutb_qmod_p") (class "Default")
      (node (ref "C77") (pin "1") (pinfunction "1_1") (pintype "passive"))
      (node (ref "C79") (pin "1") (pinfunction "1_1") (pintype "passive"))
      (node (ref "D20") (pin "10") (pinfunction "QBBP_10") (pintype "passive"))
      (node (ref "L24") (pin "2") (pinfunction "2_2") (pintype "passive"))
      (node (ref "R34") (pin "1") (pinfunction "1_1") (pintype "passive"))
    )
    (net (code "57") (name "lo1_ref_tx") (class "Default")
      (node (ref "C114") (pin "1") (pinfunction "1_1") (pintype "passive"))
      (node (ref "D24") (pin "27") (pinfunction "REF+_27") (pintype "passive"))
      (node (ref "R44") (pin "1") (pinfunction "1_1") (pintype "passive"))
    )
    (net (code "58") (name "lo2_ref_tx") (class "Default")
      (node (ref "C116") (pin "1") (pinfunction "1_1") (pintype "passive"))
      (node (ref "D23") (pin "27") (pinfunction "REF+_27") (pintype "passive"))
      (node (ref "R42") (pin "1") (pinfunction "1_1") (pintype "passive"))
    )
    (net (code "59") (name "ref_freq_tx_n") (class "Default")
      (node (ref "C115") (pin "2") (pinfunction "2_2") (pintype "passive"))
    )
    (net (code "60") (name "ref_freq_tx_p") (class "Default")
      (node (ref "C113") (pin "2") (pinfunction "2_2") (pintype "passive"))
    )
    (net (code "61") (name "unconnected-(D20-NC-Pad6)") (class "Default")
      (node (ref "D20") (pin "6") (pinfunction "NC_6") (pintype "passive+no_connect"))
    )
    (net (code "62") (name "unconnected-(D20-NC-Pad7)") (class "Default")
      (node (ref "D20") (pin "7") (pinfunction "NC_7") (pintype "passive+no_connect"))
    )
    (net (code "63") (name "unconnected-(D20-NC-Pad13)") (class "Default")
      (node (ref "D20") (pin "13") (pinfunction "NC_13") (pintype "passive+no_connect"))
    )
    (net (code "64") (name "unconnected-(D20-NC-Pad15)") (class "Default")
      (node (ref "D20") (pin "15") (pinfunction "NC_15") (pintype "passive+no_connect"))
    )
    (net (code "65") (name "unconnected-(D23A-REFO-Pad2)") (class "Default")
      (node (ref "D23") (pin "2") (pinfunction "REFO_2") (pintype "passive+no_connect"))
    )
    (net (code "66") (name "unconnected-(D24A-REFO-Pad2)") (class "Default")
      (node (ref "D24") (pin "2") (pinfunction "REFO_2") (pintype "passive+no_connect"))
    )
  )
)
